# Utility_Shield_1_2.net
KiCad netlist of a schematic drawn in EAGLE
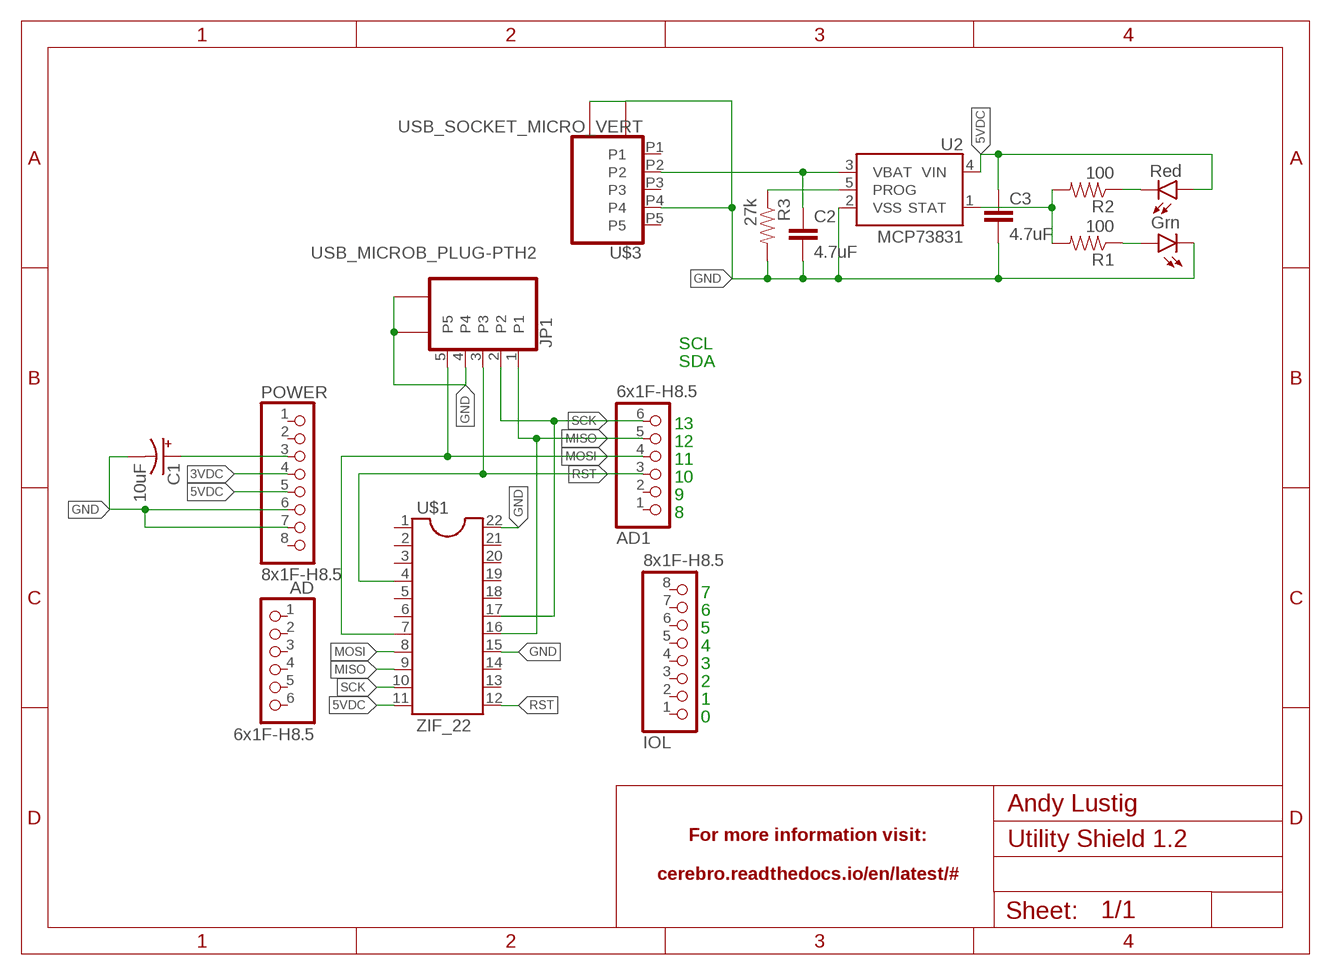
[diagram p0: schematic, sheet 1]

(export (version "E")
  (design (tool "Eeschema 10.0.6"))
  (components
    (comp (ref "AD")
      (value "6x1F-H8.5")
      (footprint "eagle-import:1X06")
      (libsource (lib "eagle-import") (part "PINHD-1X6"))
    )
    (comp (ref "AD1")
      (value "6x1F-H8.5")
      (footprint "eagle-import:1X06")
      (libsource (lib "eagle-import") (part "PINHD-1X6"))
    )
    (comp (ref "C1")
      (value "10uF")
      (footprint "eagle-import:CPOL-RADIAL-10UF-25V")
      (libsource (lib "eagle-import") (part "CAP_POLPTH2"))
    )
    (comp (ref "C2")
      (value "4.7uF")
      (footprint "eagle-import:0805")
      (libsource (lib "eagle-import") (part "1.0UF-25V-+80/-20(0805)"))
    )
    (comp (ref "C3")
      (value "4.7uF")
      (footprint "eagle-import:0805")
      (libsource (lib "eagle-import") (part "1.0UF-25V-+80/-20(0805)"))
    )
    (comp (ref "IOL")
      (value "8x1F-H8.5")
      (footprint "eagle-import:1X08")
      (libsource (lib "eagle-import") (part "PINHD-1X8"))
    )
    (comp (ref "JP1")
      (value "USB_MICROB_PLUG-PTH2")
      (footprint "eagle-import:MICRO-B-TH")
      (libsource (lib "eagle-import") (part "USB_MICROB_PLUG-PTH2"))
    )
    (comp (ref "POWER")
      (value "8x1F-H8.5")
      (footprint "eagle-import:1X08")
      (libsource (lib "eagle-import") (part "PINHD-1X8"))
    )
    (comp (ref "R1")
      (value "100")
      (footprint "eagle-import:0805")
      (libsource (lib "eagle-import") (part "RESISTOR0805-RES"))
    )
    (comp (ref "R2")
      (value "100")
      (footprint "eagle-import:0805")
      (libsource (lib "eagle-import") (part "RESISTOR0805-RES"))
    )
    (comp (ref "R3")
      (value "27k")
      (footprint "eagle-import:0805")
      (libsource (lib "eagle-import") (part "RESISTOR0805-RES"))
    )
    (comp (ref "U$1")
      (value "ZIF_22")
      (footprint "eagle-import:ZIF_22")
      (libsource (lib "eagle-import") (part "ZIF_22"))
    )
    (comp (ref "U$2")
      (value "LED_DUAL")
      (footprint "eagle-import:LED_DUAL")
      (libsource (lib "eagle-import") (part "LED_DUAL"))
    )
    (comp (ref "U$3")
      (value "USB_SOCKET_MICRO_VERT")
      (footprint "eagle-import:USB_VERT_MICRO_SMD")
      (libsource (lib "eagle-import") (part "USB_SOCKET_MICRO_VERT"))
    )
    (comp (ref "U2")
      (value "MCP73831")
      (footprint "eagle-import:SOT23-5")
      (libsource (lib "eagle-import") (part "MCP73831"))
    )
  )
  (nets
    (net (code "1") (name "3VDC") (class "Default")
      (node (ref "POWER") (pin "4") (pinfunction "4_4") (pintype "passive"))
    )
    (net (code "2") (name "5VDC") (class "Default")
      (node (ref "C3") (pin "1") (pinfunction "1_1") (pintype "passive"))
      (node (ref "POWER") (pin "5") (pinfunction "5_5") (pintype "passive"))
      (node (ref "U$1") (pin "11") (pinfunction "11_11") (pintype "passive"))
      (node (ref "U$2") (pin "RA") (pinfunction "RA_RA") (pintype "passive"))
      (node (ref "U2") (pin "4") (pinfunction "VIN_4") (pintype "power_in"))
    )
    (net (code "3") (name "GND") (class "Default")
      (node (ref "C1") (pin "2") (pinfunction "-_2") (pintype "passive"))
      (node (ref "C2") (pin "2") (pinfunction "2_2") (pintype "passive"))
      (node (ref "C3") (pin "2") (pinfunction "2_2") (pintype "passive"))
      (node (ref "JP1") (pin "4") (pinfunction "P4_4") (pintype "bidirectional"))
      (node (ref "JP1") (pin "P$1") (pinfunction "P$1_P$1") (pintype "bidirectional"))
      (node (ref "JP1") (pin "P$2") (pinfunction "P$2_P$2") (pintype "bidirectional"))
      (node (ref "POWER") (pin "6") (pinfunction "6_6") (pintype "passive"))
      (node (ref "POWER") (pin "7") (pinfunction "7_7") (pintype "passive"))
      (node (ref "R3") (pin "2") (pinfunction "2_2") (pintype "passive"))
      (node (ref "U$1") (pin "15") (pinfunction "15_15") (pintype "passive"))
      (node (ref "U$1") (pin "22") (pinfunction "22_22") (pintype "passive"))
      (node (ref "U$2") (pin "GC") (pinfunction "GC_GC") (pintype "passive"))
      (node (ref "U$3") (pin "P$1") (pinfunction "P$1_P$1") (pintype "bidirectional"))
      (node (ref "U$3") (pin "P$2") (pinfunction "P$2_P$2") (pintype "bidirectional"))
      (node (ref "U$3") (pin "P$3") (pinfunction "P$2_P$3") (pintype "bidirectional"))
      (node (ref "U$3") (pin "P4") (pinfunction "P4_P4") (pintype "bidirectional"))
      (node (ref "U2") (pin "2") (pinfunction "VSS_2") (pintype "power_in"))
    )
    (net (code "4") (name "MISO") (class "Default")
      (node (ref "AD1") (pin "5") (pinfunction "5_5") (pintype "passive"))
      (node (ref "JP1") (pin "1") (pinfunction "P1_1") (pintype "bidirectional"))
      (node (ref "U$1") (pin "16") (pinfunction "16_16") (pintype "passive"))
      (node (ref "U$1") (pin "9") (pinfunction "9_9") (pintype "passive"))
    )
    (net (code "5") (name "MOSI") (class "Default")
      (node (ref "AD1") (pin "4") (pinfunction "4_4") (pintype "passive"))
      (node (ref "JP1") (pin "5") (pinfunction "P5_5") (pintype "bidirectional"))
      (node (ref "U$1") (pin "7") (pinfunction "7_7") (pintype "passive"))
      (node (ref "U$1") (pin "8") (pinfunction "8_8") (pintype "passive"))
    )
    (net (code "6") (name "Net-(C1-+)") (class "Default")
      (node (ref "C1") (pin "1") (pinfunction "+_1") (pintype "passive"))
      (node (ref "POWER") (pin "3") (pinfunction "3_3") (pintype "passive"))
    )
    (net (code "7") (name "Net-(R1-Pad1)") (class "Default")
      (node (ref "R1") (pin "1") (pinfunction "1_1") (pintype "passive"))
      (node (ref "U$2") (pin "GA") (pinfunction "GA_GA") (pintype "passive"))
    )
    (net (code "8") (name "Net-(R2-Pad1)") (class "Default")
      (node (ref "R2") (pin "1") (pinfunction "1_1") (pintype "passive"))
      (node (ref "U$2") (pin "RC") (pinfunction "RC_RC") (pintype "passive"))
    )
    (net (code "9") (name "Net-(U2-PROG)") (class "Default")
      (node (ref "R3") (pin "1") (pinfunction "1_1") (pintype "passive"))
      (node (ref "U2") (pin "5") (pinfunction "PROG_5") (pintype "input"))
    )
    (net (code "10") (name "Net-(U2-STAT)") (class "Default")
      (node (ref "R1") (pin "2") (pinfunction "2_2") (pintype "passive"))
      (node (ref "R2") (pin "2") (pinfunction "2_2") (pintype "passive"))
      (node (ref "U2") (pin "1") (pinfunction "STAT_1") (pintype "output"))
    )
    (net (code "11") (name "Net-(U2-VBAT)") (class "Default")
      (node (ref "C2") (pin "1") (pinfunction "1_1") (pintype "passive"))
      (node (ref "U$3") (pin "P2") (pinfunction "P2_P2") (pintype "bidirectional"))
      (node (ref "U2") (pin "3") (pinfunction "VBAT_3") (pintype "power_in"))
    )
    (net (code "12") (name "RST") (class "Default")
      (node (ref "AD1") (pin "3") (pinfunction "3_3") (pintype "passive"))
      (node (ref "JP1") (pin "3") (pinfunction "P3_3") (pintype "bidirectional"))
      (node (ref "U$1") (pin "12") (pinfunction "12_12") (pintype "passive"))
      (node (ref "U$1") (pin "4") (pinfunction "4_4") (pintype "passive"))
    )
    (net (code "13") (name "SCK") (class "Default")
      (node (ref "AD1") (pin "6") (pinfunction "6_6") (pintype "passive"))
      (node (ref "JP1") (pin "2") (pinfunction "P2_2") (pintype "bidirectional"))
      (node (ref "U$1") (pin "10") (pinfunction "10_10") (pintype "passive"))
      (node (ref "U$1") (pin "17") (pinfunction "17_17") (pintype "passive"))
    )
    (net (code "14") (name "unconnected-(AD-Pad1)") (class "Default")
      (node (ref "AD") (pin "1") (pinfunction "1_1") (pintype "passive"))
    )
    (net (code "15") (name "unconnected-(AD-Pad2)") (class "Default")
      (node (ref "AD") (pin "2") (pinfunction "2_2") (pintype "passive"))
    )
    (net (code "16") (name "unconnected-(AD-Pad3)") (class "Default")
      (node (ref "AD") (pin "3") (pinfunction "3_3") (pintype "passive"))
    )
    (net (code "17") (name "unconnected-(AD-Pad4)") (class "Default")
      (node (ref "AD") (pin "4") (pinfunction "4_4") (pintype "passive"))
    )
    (net (code "18") (name "unconnected-(AD-Pad5)") (class "Default")
      (node (ref "AD") (pin "5") (pinfunction "5_5") (pintype "passive"))
    )
    (net (code "19") (name "unconnected-(AD-Pad6)") (class "Default")
      (node (ref "AD") (pin "6") (pinfunction "6_6") (pintype "passive"))
    )
    (net (code "20") (name "unconnected-(AD1-Pad1)") (class "Default")
      (node (ref "AD1") (pin "1") (pinfunction "1_1") (pintype "passive"))
    )
    (net (code "21") (name "unconnected-(AD1-Pad2)") (class "Default")
      (node (ref "AD1") (pin "2") (pinfunction "2_2") (pintype "passive"))
    )
    (net (code "22") (name "unconnected-(IOL-Pad1)") (class "Default")
      (node (ref "IOL") (pin "1") (pinfunction "1_1") (pintype "passive"))
    )
    (net (code "23") (name "unconnected-(IOL-Pad2)") (class "Default")
      (node (ref "IOL") (pin "2") (pinfunction "2_2") (pintype "passive"))
    )
    (net (code "24") (name "unconnected-(IOL-Pad3)") (class "Default")
      (node (ref "IOL") (pin "3") (pinfunction "3_3") (pintype "passive"))
    )
    (net (code "25") (name "unconnected-(IOL-Pad4)") (class "Default")
      (node (ref "IOL") (pin "4") (pinfunction "4_4") (pintype "passive"))
    )
    (net (code "26") (name "unconnected-(IOL-Pad5)") (class "Default")
      (node (ref "IOL") (pin "5") (pinfunction "5_5") (pintype "passive"))
    )
    (net (code "27") (name "unconnected-(IOL-Pad6)") (class "Default")
      (node (ref "IOL") (pin "6") (pinfunction "6_6") (pintype "passive"))
    )
    (net (code "28") (name "unconnected-(IOL-Pad7)") (class "Default")
      (node (ref "IOL") (pin "7") (pinfunction "7_7") (pintype "passive"))
    )
    (net (code "29") (name "unconnected-(IOL-Pad8)") (class "Default")
      (node (ref "IOL") (pin "8") (pinfunction "8_8") (pintype "passive"))
    )
    (net (code "30") (name "unconnected-(POWER-Pad1)") (class "Default")
      (node (ref "POWER") (pin "1") (pinfunction "1_1") (pintype "passive"))
    )
    (net (code "31") (name "unconnected-(POWER-Pad2)") (class "Default")
      (node (ref "POWER") (pin "2") (pinfunction "2_2") (pintype "passive"))
    )
    (net (code "32") (name "unconnected-(POWER-Pad8)") (class "Default")
      (node (ref "POWER") (pin "8") (pinfunction "8_8") (pintype "passive"))
    )
    (net (code "33") (name "unconnected-(U$1-Pad1)") (class "Default")
      (node (ref "U$1") (pin "1") (pinfunction "1_1") (pintype "passive"))
    )
    (net (code "34") (name "unconnected-(U$1-Pad2)") (class "Default")
      (node (ref "U$1") (pin "2") (pinfunction "2_2") (pintype "passive"))
    )
    (net (code "35") (name "unconnected-(U$1-Pad3)") (class "Default")
      (node (ref "U$1") (pin "3") (pinfunction "3_3") (pintype "passive"))
    )
    (net (code "36") (name "unconnected-(U$1-Pad5)") (class "Default")
      (node (ref "U$1") (pin "5") (pinfunction "5_5") (pintype "passive"))
    )
    (net (code "37") (name "unconnected-(U$1-Pad6)") (class "Default")
      (node (ref "U$1") (pin "6") (pinfunction "6_6") (pintype "passive"))
    )
    (net (code "38") (name "unconnected-(U$1-Pad13)") (class "Default")
      (node (ref "U$1") (pin "13") (pinfunction "13_13") (pintype "passive"))
    )
    (net (code "39") (name "unconnected-(U$1-Pad14)") (class "Default")
      (node (ref "U$1") (pin "14") (pinfunction "14_14") (pintype "passive"))
    )
    (net (code "40") (name "unconnected-(U$1-Pad18)") (class "Default")
      (node (ref "U$1") (pin "18") (pinfunction "18_18") (pintype "passive"))
    )
    (net (code "41") (name "unconnected-(U$1-Pad19)") (class "Default")
      (node (ref "U$1") (pin "19") (pinfunction "19_19") (pintype "passive"))
    )
    (net (code "42") (name "unconnected-(U$1-Pad20)") (class "Default")
      (node (ref "U$1") (pin "20") (pinfunction "20_20") (pintype "passive"))
    )
    (net (code "43") (name "unconnected-(U$1-Pad21)") (class "Default")
      (node (ref "U$1") (pin "21") (pinfunction "21_21") (pintype "passive"))
    )
    (net (code "44") (name "unconnected-(U$3-PadP1)") (class "Default")
      (node (ref "U$3") (pin "P1") (pinfunction "P1_P1") (pintype "bidirectional"))
    )
    (net (code "45") (name "unconnected-(U$3-PadP3)") (class "Default")
      (node (ref "U$3") (pin "P3") (pinfunction "P3_P3") (pintype "bidirectional"))
    )
    (net (code "46") (name "unconnected-(U$3-PadP5)") (class "Default")
      (node (ref "U$3") (pin "P5") (pinfunction "P5_P5") (pintype "bidirectional"))
    )
  )
)
